# BoostConverter.net
KiCad netlist of a schematic drawn in EAGLE
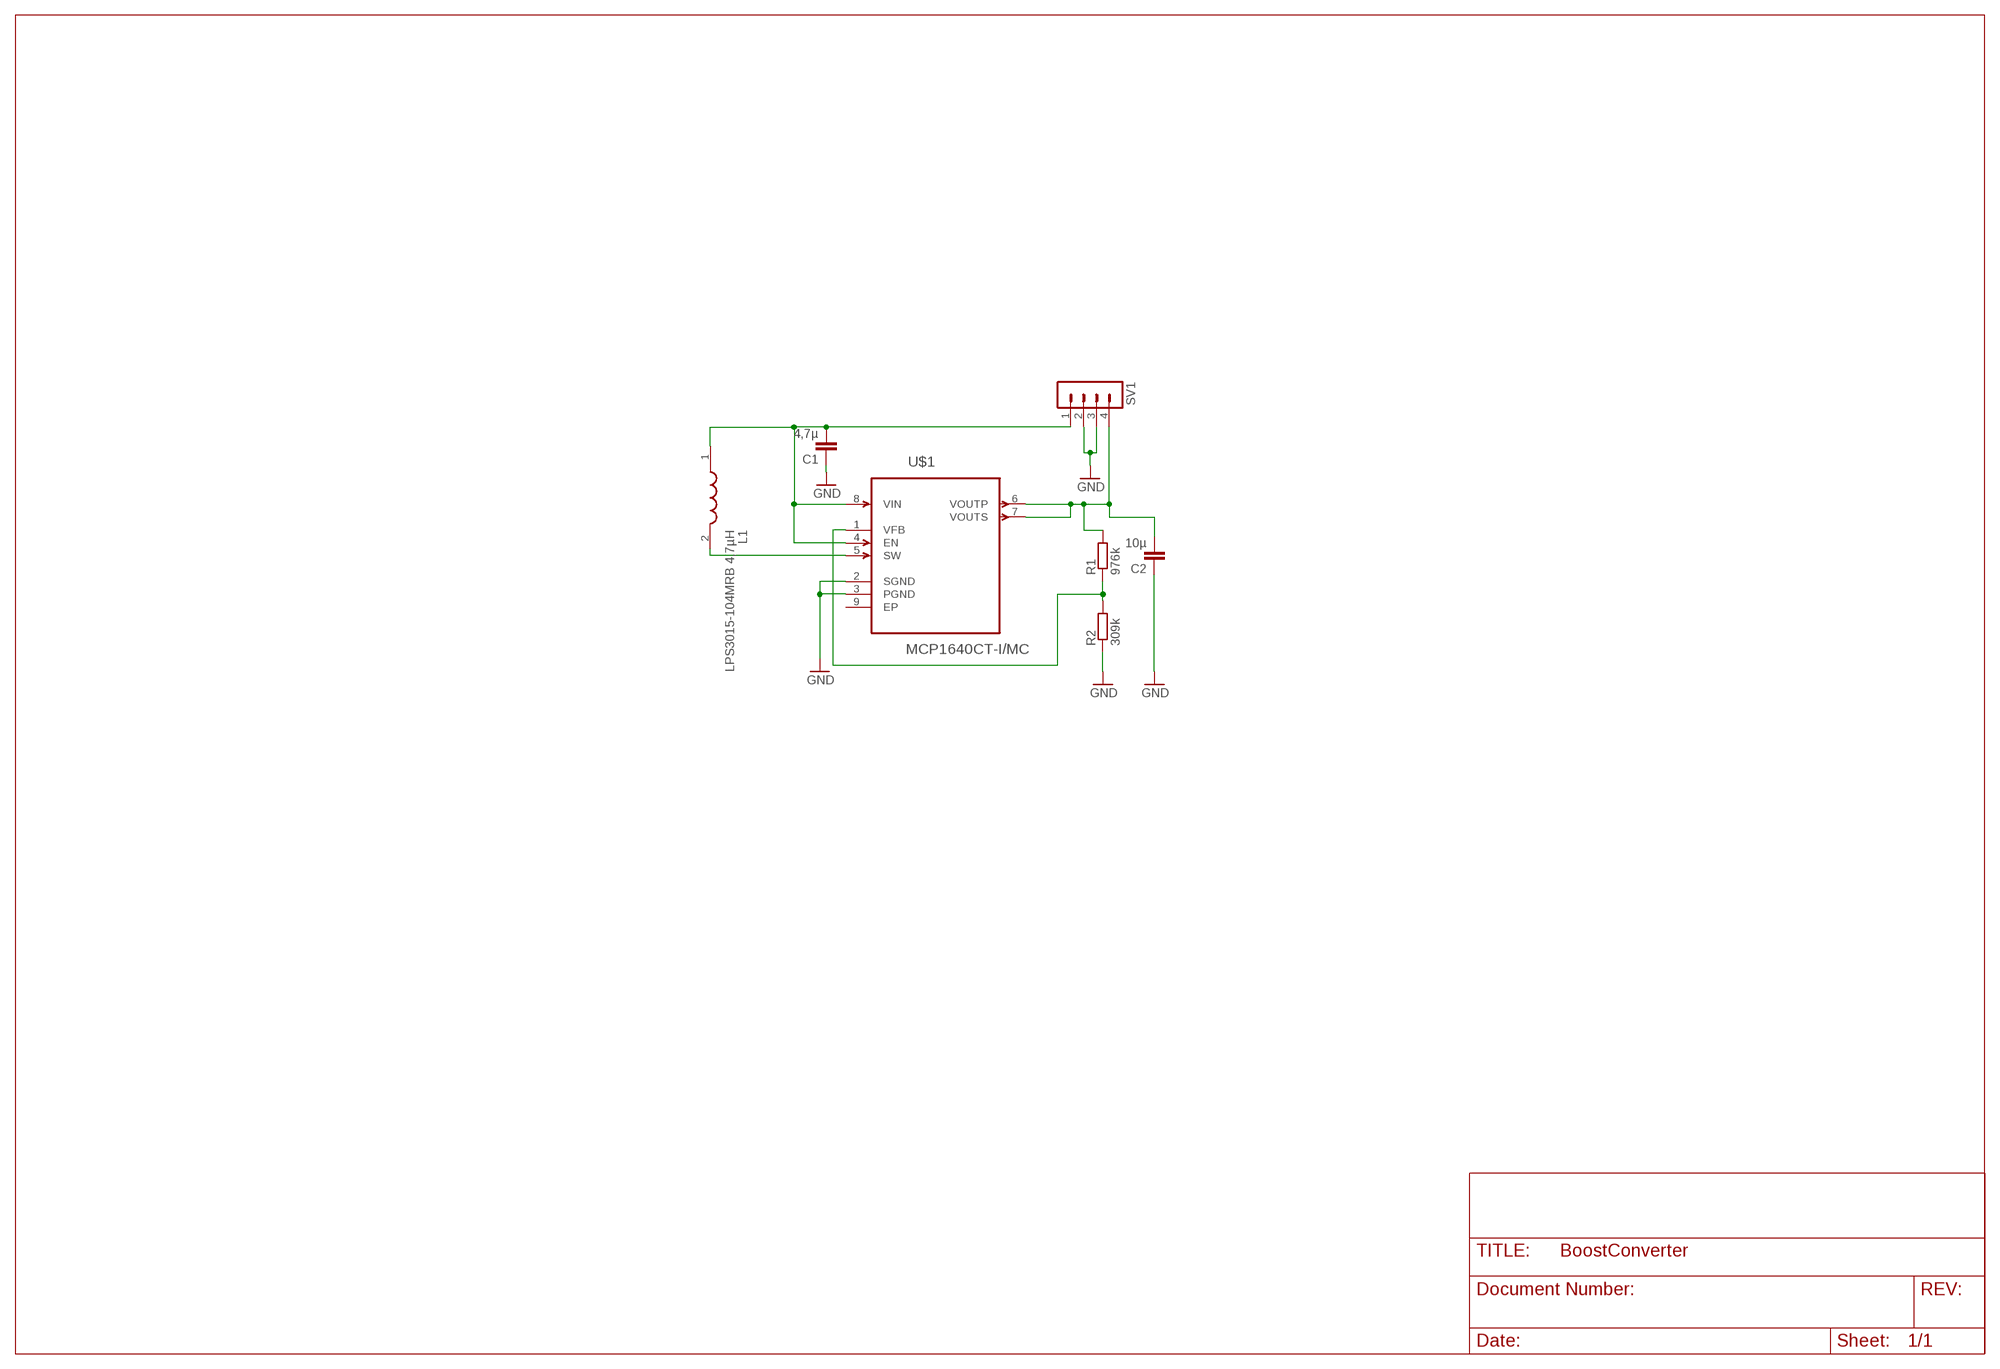
[diagram p0: schematic, sheet 1]

(export (version "E")
  (design (tool "Eeschema 10.0.6"))
  (components
    (comp (ref "C1")
      (value "4,7µ")
      (footprint "eagle-import:C0603")
      (libsource (lib "eagle-import") (part "C-EUC0603"))
    )
    (comp (ref "C2")
      (value "10µ")
      (footprint "eagle-import:C0603")
      (libsource (lib "eagle-import") (part "C-EUC0603"))
    )
    (comp (ref "L1")
      (value "LPS3015-104MRB 4,7µH")
      (footprint "eagle-import:LPS3015")
      (fields (field (name "MF") "Coilcraft") (field (name "MP") "LPS3015-104MRB"))
      (libsource (lib "eagle-import") (part "LPS3015-104MRB"))
    )
    (comp (ref "R1")
      (value "976k")
      (footprint "eagle-import:R0603")
      (libsource (lib "eagle-import") (part "R-EU_R0603"))
    )
    (comp (ref "R2")
      (value "309k")
      (footprint "eagle-import:R0603")
      (libsource (lib "eagle-import") (part "R-EU_R0603"))
    )
    (comp (ref "SV1")
      (value "MA04-1")
      (footprint "eagle-import:MA04-1")
      (libsource (lib "eagle-import") (part "MA04-1"))
    )
    (comp (ref "U$1")
      (value "MCP1640CT-I/MC")
      (footprint "eagle-import:DFN200X300X100-9N")
      (fields (field (name "MF") "Microchip"))
      (libsource (lib "eagle-import") (part "MCP1640CT-I/MC"))
    )
  )
  (nets
    (net (code "1") (name "GND") (class "Default")
      (node (ref "C1") (pin "1") (pinfunction "1_1") (pintype "passive"))
      (node (ref "C2") (pin "1") (pinfunction "1_1") (pintype "passive"))
      (node (ref "R2") (pin "1") (pinfunction "1_1") (pintype "passive"))
      (node (ref "SV1") (pin "2") (pinfunction "2_2") (pintype "passive"))
      (node (ref "SV1") (pin "3") (pinfunction "3_3") (pintype "passive"))
      (node (ref "U$1") (pin "2") (pinfunction "SGND_2") (pintype "power_in"))
      (node (ref "U$1") (pin "3") (pinfunction "PGND_3") (pintype "power_in"))
    )
    (net (code "2") (name "Net-(U$1-EN)") (class "Default")
      (node (ref "C1") (pin "2") (pinfunction "2_2") (pintype "passive"))
      (node (ref "L1") (pin "1") (pinfunction "1_1") (pintype "bidirectional"))
      (node (ref "SV1") (pin "1") (pinfunction "1_1") (pintype "passive"))
      (node (ref "U$1") (pin "4") (pinfunction "EN_4") (pintype "input"))
      (node (ref "U$1") (pin "8") (pinfunction "VIN_8") (pintype "input"))
    )
    (net (code "3") (name "Net-(U$1-SW)") (class "Default")
      (node (ref "L1") (pin "2") (pinfunction "2_2") (pintype "bidirectional"))
      (node (ref "U$1") (pin "5") (pinfunction "SW_5") (pintype "input"))
    )
    (net (code "4") (name "Net-(U$1-VFB)") (class "Default")
      (node (ref "R1") (pin "1") (pinfunction "1_1") (pintype "passive"))
      (node (ref "R2") (pin "2") (pinfunction "2_2") (pintype "passive"))
      (node (ref "U$1") (pin "1") (pinfunction "VFB_1") (pintype "input"))
    )
    (net (code "5") (name "Net-(U$1-VOUTP)") (class "Default")
      (node (ref "C2") (pin "2") (pinfunction "2_2") (pintype "passive"))
      (node (ref "R1") (pin "2") (pinfunction "2_2") (pintype "passive"))
      (node (ref "SV1") (pin "4") (pinfunction "4_4") (pintype "passive"))
      (node (ref "U$1") (pin "6") (pinfunction "VOUTP_6") (pintype "output"))
      (node (ref "U$1") (pin "7") (pinfunction "VOUTS_7") (pintype "output"))
    )
    (net (code "6") (name "unconnected-(U$1-EP-Pad9)") (class "Default")
      (node (ref "U$1") (pin "9") (pinfunction "EP_9") (pintype "passive"))
    )
  )
)
